# rel-cu.net
KiCad netlist of a schematic drawn in EAGLE
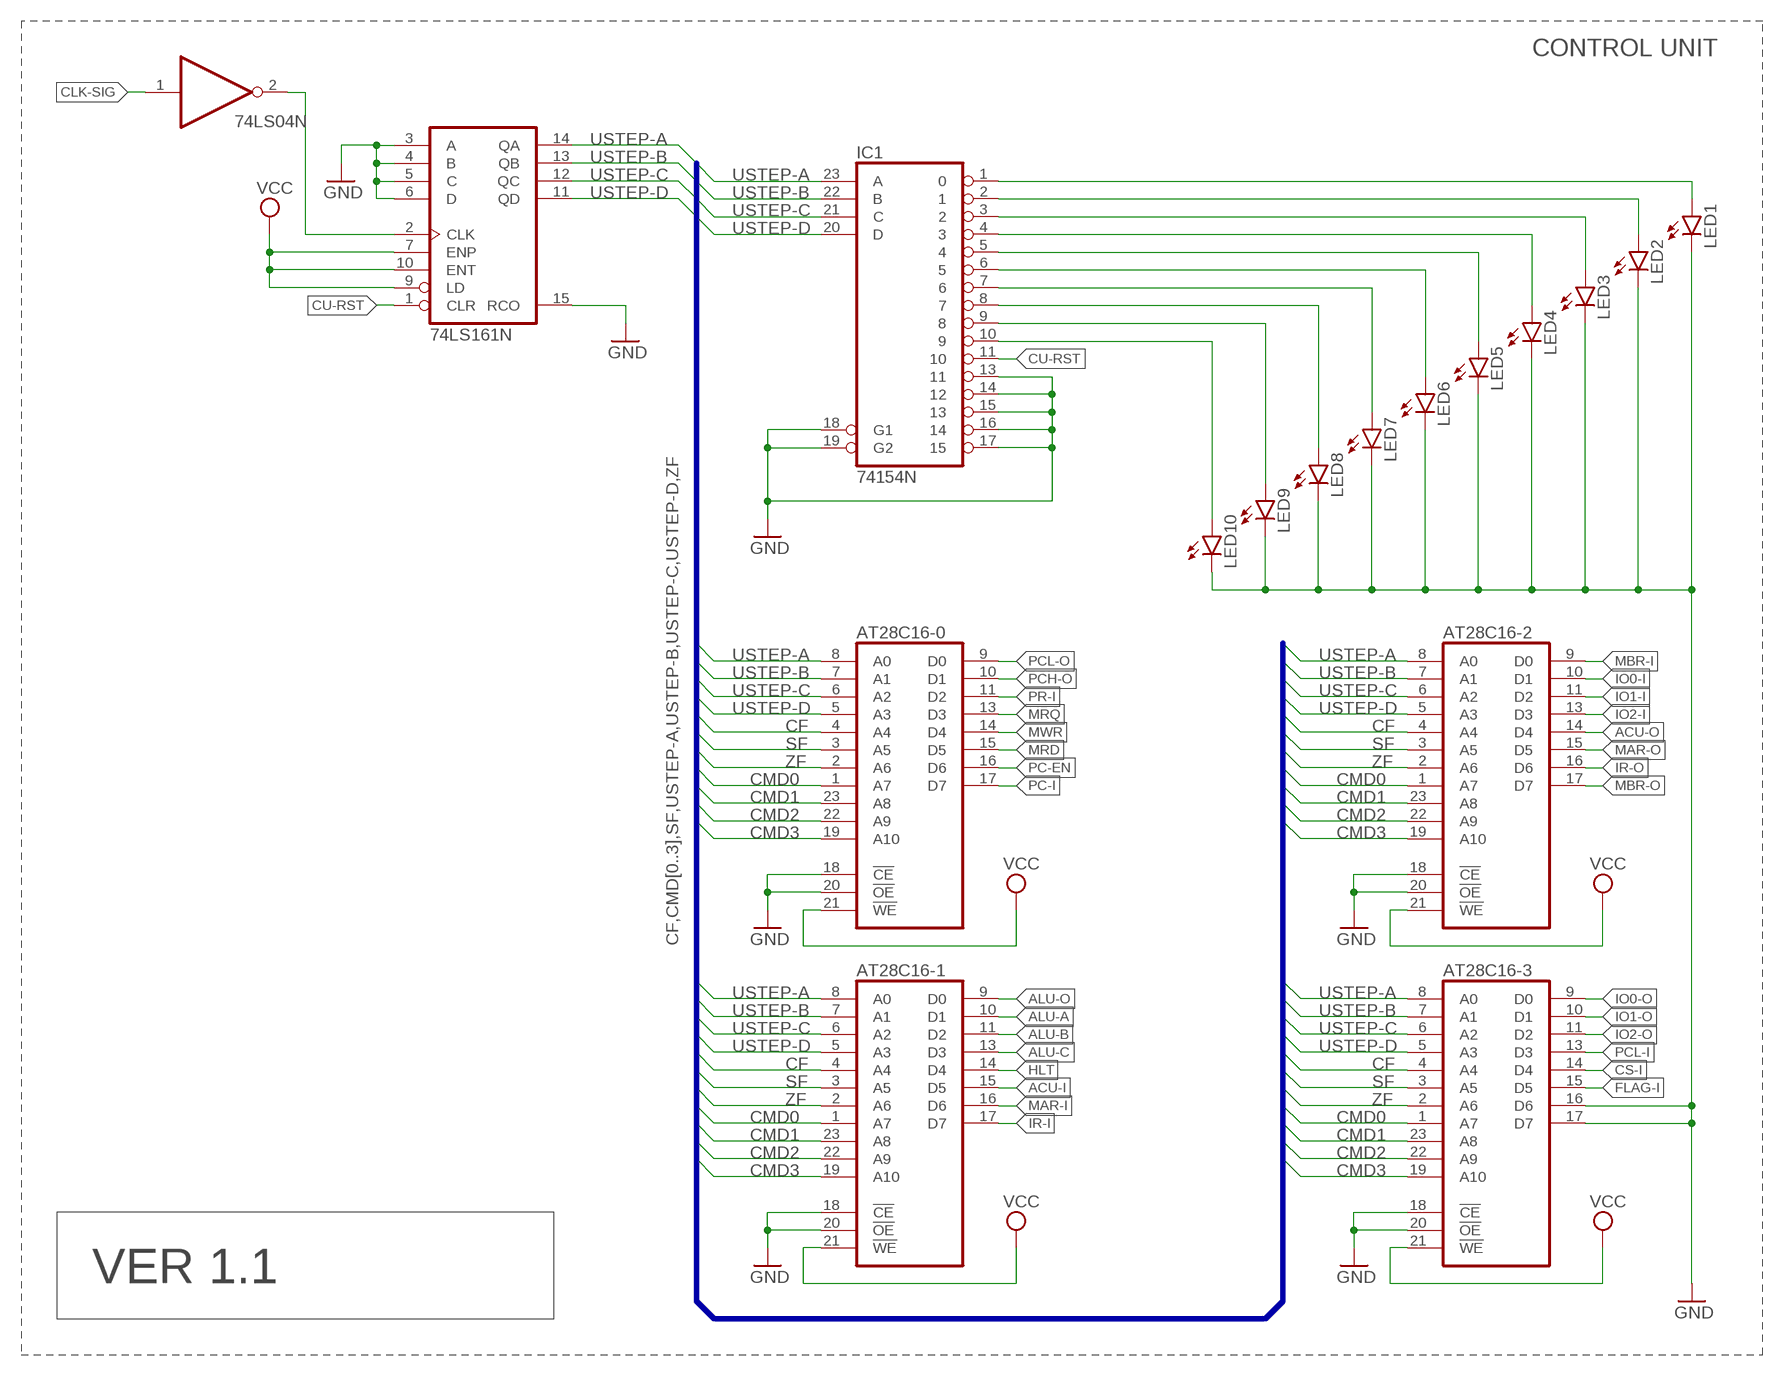
[diagram p0: schematic, sheet 1]

(export (version "E")
  (design (tool "Eeschema 10.0.6"))
  (components
    (comp (ref "74LS161N")
      (value "74160N")
      (footprint "eagle-import:DIL16")
      (libsource (lib "eagle-import") (part "74160N"))
    )
    (comp (ref "AT28C16-0")
      (value "2816")
      (footprint "eagle-import:DIL24")
      (libsource (lib "eagle-import") (part "2816"))
    )
    (comp (ref "AT28C16-1")
      (value "2816")
      (footprint "eagle-import:DIL24")
      (libsource (lib "eagle-import") (part "2816"))
    )
    (comp (ref "AT28C16-2")
      (value "2816")
      (footprint "eagle-import:DIL24")
      (libsource (lib "eagle-import") (part "2816"))
    )
    (comp (ref "AT28C16-3")
      (value "2816")
      (footprint "eagle-import:DIL24")
      (libsource (lib "eagle-import") (part "2816"))
    )
    (comp (ref "IC1")
      (value "74154N")
      (footprint "eagle-import:DIL24-6")
      (libsource (lib "eagle-import") (part "74154N"))
    )
    (comp (ref "IC2")
      (value "74LS04N")
      (footprint "eagle-import:DIL14")
      (libsource (lib "eagle-import") (part "7404NLS"))
    )
    (comp (ref "LED1")
      (value "LED5MM")
      (footprint "eagle-import:LED5MM")
      (libsource (lib "eagle-import") (part "LED5MM"))
    )
    (comp (ref "LED2")
      (value "LED5MM")
      (footprint "eagle-import:LED5MM")
      (libsource (lib "eagle-import") (part "LED5MM"))
    )
    (comp (ref "LED3")
      (value "LED5MM")
      (footprint "eagle-import:LED5MM")
      (libsource (lib "eagle-import") (part "LED5MM"))
    )
    (comp (ref "LED4")
      (value "LED5MM")
      (footprint "eagle-import:LED5MM")
      (libsource (lib "eagle-import") (part "LED5MM"))
    )
    (comp (ref "LED5")
      (value "LED5MM")
      (footprint "eagle-import:LED5MM")
      (libsource (lib "eagle-import") (part "LED5MM"))
    )
    (comp (ref "LED6")
      (value "LED5MM")
      (footprint "eagle-import:LED5MM")
      (libsource (lib "eagle-import") (part "LED5MM"))
    )
    (comp (ref "LED7")
      (value "LED5MM")
      (footprint "eagle-import:LED5MM")
      (libsource (lib "eagle-import") (part "LED5MM"))
    )
    (comp (ref "LED8")
      (value "LED5MM")
      (footprint "eagle-import:LED5MM")
      (libsource (lib "eagle-import") (part "LED5MM"))
    )
    (comp (ref "LED9")
      (value "LED5MM")
      (footprint "eagle-import:LED5MM")
      (libsource (lib "eagle-import") (part "LED5MM"))
    )
    (comp (ref "LED10")
      (value "LED5MM")
      (footprint "eagle-import:LED5MM")
      (libsource (lib "eagle-import") (part "LED5MM"))
    )
  )
  (nets
    (net (code "1") (name "/CF") (class "Default")
      (node (ref "AT28C16-0") (pin "4") (pinfunction "A4_4") (pintype "input"))
      (node (ref "AT28C16-1") (pin "4") (pinfunction "A4_4") (pintype "input"))
      (node (ref "AT28C16-2") (pin "4") (pinfunction "A4_4") (pintype "input"))
      (node (ref "AT28C16-3") (pin "4") (pinfunction "A4_4") (pintype "input"))
    )
    (net (code "2") (name "/CMD0") (class "Default")
      (node (ref "AT28C16-0") (pin "1") (pinfunction "A7_1") (pintype "input"))
      (node (ref "AT28C16-1") (pin "1") (pinfunction "A7_1") (pintype "input"))
      (node (ref "AT28C16-2") (pin "1") (pinfunction "A7_1") (pintype "input"))
      (node (ref "AT28C16-3") (pin "1") (pinfunction "A7_1") (pintype "input"))
    )
    (net (code "3") (name "/CMD1") (class "Default")
      (node (ref "AT28C16-0") (pin "23") (pinfunction "A8_23") (pintype "input"))
      (node (ref "AT28C16-1") (pin "23") (pinfunction "A8_23") (pintype "input"))
      (node (ref "AT28C16-2") (pin "23") (pinfunction "A8_23") (pintype "input"))
      (node (ref "AT28C16-3") (pin "23") (pinfunction "A8_23") (pintype "input"))
    )
    (net (code "4") (name "/CMD2") (class "Default")
      (node (ref "AT28C16-0") (pin "22") (pinfunction "A9_22") (pintype "input"))
      (node (ref "AT28C16-1") (pin "22") (pinfunction "A9_22") (pintype "input"))
      (node (ref "AT28C16-2") (pin "22") (pinfunction "A9_22") (pintype "input"))
      (node (ref "AT28C16-3") (pin "22") (pinfunction "A9_22") (pintype "input"))
    )
    (net (code "5") (name "/CMD3") (class "Default")
      (node (ref "AT28C16-0") (pin "19") (pinfunction "A10_19") (pintype "input"))
      (node (ref "AT28C16-1") (pin "19") (pinfunction "A10_19") (pintype "input"))
      (node (ref "AT28C16-2") (pin "19") (pinfunction "A10_19") (pintype "input"))
      (node (ref "AT28C16-3") (pin "19") (pinfunction "A10_19") (pintype "input"))
    )
    (net (code "6") (name "/SF") (class "Default")
      (node (ref "AT28C16-0") (pin "3") (pinfunction "A5_3") (pintype "input"))
      (node (ref "AT28C16-1") (pin "3") (pinfunction "A5_3") (pintype "input"))
      (node (ref "AT28C16-2") (pin "3") (pinfunction "A5_3") (pintype "input"))
      (node (ref "AT28C16-3") (pin "3") (pinfunction "A5_3") (pintype "input"))
    )
    (net (code "7") (name "/USTEP-A") (class "Default")
      (node (ref "74LS161N") (pin "14") (pinfunction "QA_14") (pintype "output"))
      (node (ref "AT28C16-0") (pin "8") (pinfunction "A0_8") (pintype "input"))
      (node (ref "AT28C16-1") (pin "8") (pinfunction "A0_8") (pintype "input"))
      (node (ref "AT28C16-2") (pin "8") (pinfunction "A0_8") (pintype "input"))
      (node (ref "AT28C16-3") (pin "8") (pinfunction "A0_8") (pintype "input"))
      (node (ref "IC1") (pin "23") (pinfunction "A_23") (pintype "input"))
    )
    (net (code "8") (name "/USTEP-B") (class "Default")
      (node (ref "74LS161N") (pin "13") (pinfunction "QB_13") (pintype "output"))
      (node (ref "AT28C16-0") (pin "7") (pinfunction "A1_7") (pintype "input"))
      (node (ref "AT28C16-1") (pin "7") (pinfunction "A1_7") (pintype "input"))
      (node (ref "AT28C16-2") (pin "7") (pinfunction "A1_7") (pintype "input"))
      (node (ref "AT28C16-3") (pin "7") (pinfunction "A1_7") (pintype "input"))
      (node (ref "IC1") (pin "22") (pinfunction "B_22") (pintype "input"))
    )
    (net (code "9") (name "/USTEP-C") (class "Default")
      (node (ref "74LS161N") (pin "12") (pinfunction "QC_12") (pintype "output"))
      (node (ref "AT28C16-0") (pin "6") (pinfunction "A2_6") (pintype "input"))
      (node (ref "AT28C16-1") (pin "6") (pinfunction "A2_6") (pintype "input"))
      (node (ref "AT28C16-2") (pin "6") (pinfunction "A2_6") (pintype "input"))
      (node (ref "AT28C16-3") (pin "6") (pinfunction "A2_6") (pintype "input"))
      (node (ref "IC1") (pin "21") (pinfunction "C_21") (pintype "input"))
    )
    (net (code "10") (name "/USTEP-D") (class "Default")
      (node (ref "74LS161N") (pin "11") (pinfunction "QD_11") (pintype "output"))
      (node (ref "AT28C16-0") (pin "5") (pinfunction "A3_5") (pintype "input"))
      (node (ref "AT28C16-1") (pin "5") (pinfunction "A3_5") (pintype "input"))
      (node (ref "AT28C16-2") (pin "5") (pinfunction "A3_5") (pintype "input"))
      (node (ref "AT28C16-3") (pin "5") (pinfunction "A3_5") (pintype "input"))
      (node (ref "IC1") (pin "20") (pinfunction "D_20") (pintype "input"))
    )
    (net (code "11") (name "/ZF") (class "Default")
      (node (ref "AT28C16-0") (pin "2") (pinfunction "A6_2") (pintype "input"))
      (node (ref "AT28C16-1") (pin "2") (pinfunction "A6_2") (pintype "input"))
      (node (ref "AT28C16-2") (pin "2") (pinfunction "A6_2") (pintype "input"))
      (node (ref "AT28C16-3") (pin "2") (pinfunction "A6_2") (pintype "input"))
    )
    (net (code "13") (name "ACU-I") (class "Default")
      (node (ref "AT28C16-1") (pin "15") (pinfunction "D5_15") (pintype "bidirectional"))
    )
    (net (code "14") (name "ACU-O") (class "Default")
      (node (ref "AT28C16-2") (pin "14") (pinfunction "D4_14") (pintype "bidirectional"))
    )
    (net (code "15") (name "ALU-A") (class "Default")
      (node (ref "AT28C16-1") (pin "10") (pinfunction "D1_10") (pintype "bidirectional"))
    )
    (net (code "16") (name "ALU-B") (class "Default")
      (node (ref "AT28C16-1") (pin "11") (pinfunction "D2_11") (pintype "bidirectional"))
    )
    (net (code "17") (name "ALU-C") (class "Default")
      (node (ref "AT28C16-1") (pin "13") (pinfunction "D3_13") (pintype "bidirectional"))
    )
    (net (code "18") (name "ALU-O") (class "Default")
      (node (ref "AT28C16-1") (pin "9") (pinfunction "D0_9") (pintype "bidirectional"))
    )
    (net (code "19") (name "CLK-SIG") (class "Default")
      (node (ref "74LS161N") (pin "2") (pinfunction "CLK_2") (pintype "input"))
      (node (ref "IC2") (pin "1") (pinfunction "I_1") (pintype "input"))
      (node (ref "IC2") (pin "2") (pinfunction "O_2") (pintype "output"))
    )
    (net (code "20") (name "CS-I") (class "Default")
      (node (ref "AT28C16-3") (pin "14") (pinfunction "D4_14") (pintype "bidirectional"))
    )
    (net (code "21") (name "CU-RST") (class "Default")
      (node (ref "74LS161N") (pin "1") (pinfunction "CLR_1") (pintype "input"))
      (node (ref "IC1") (pin "11") (pinfunction "10_11") (pintype "output"))
    )
    (net (code "22") (name "FLAG-I") (class "Default")
      (node (ref "AT28C16-3") (pin "15") (pinfunction "D5_15") (pintype "bidirectional"))
    )
    (net (code "23") (name "GND") (class "Default")
      (node (ref "74LS161N") (pin "15") (pinfunction "RCO_15") (pintype "output"))
      (node (ref "74LS161N") (pin "3") (pinfunction "A_3") (pintype "input"))
      (node (ref "74LS161N") (pin "4") (pinfunction "B_4") (pintype "input"))
      (node (ref "74LS161N") (pin "5") (pinfunction "C_5") (pintype "input"))
      (node (ref "74LS161N") (pin "6") (pinfunction "D_6") (pintype "input"))
      (node (ref "AT28C16-0") (pin "18") (pinfunction "~{CE}_18") (pintype "input"))
      (node (ref "AT28C16-0") (pin "20") (pinfunction "~{OE}_20") (pintype "input"))
      (node (ref "AT28C16-1") (pin "18") (pinfunction "~{CE}_18") (pintype "input"))
      (node (ref "AT28C16-1") (pin "20") (pinfunction "~{OE}_20") (pintype "input"))
      (node (ref "AT28C16-2") (pin "18") (pinfunction "~{CE}_18") (pintype "input"))
      (node (ref "AT28C16-2") (pin "20") (pinfunction "~{OE}_20") (pintype "input"))
      (node (ref "AT28C16-3") (pin "16") (pinfunction "D6_16") (pintype "bidirectional"))
      (node (ref "AT28C16-3") (pin "17") (pinfunction "D7_17") (pintype "bidirectional"))
      (node (ref "AT28C16-3") (pin "18") (pinfunction "~{CE}_18") (pintype "input"))
      (node (ref "AT28C16-3") (pin "20") (pinfunction "~{OE}_20") (pintype "input"))
      (node (ref "IC1") (pin "13") (pinfunction "11_13") (pintype "output"))
      (node (ref "IC1") (pin "14") (pinfunction "12_14") (pintype "output"))
      (node (ref "IC1") (pin "15") (pinfunction "13_15") (pintype "output"))
      (node (ref "IC1") (pin "16") (pinfunction "14_16") (pintype "output"))
      (node (ref "IC1") (pin "17") (pinfunction "15_17") (pintype "output"))
      (node (ref "IC1") (pin "18") (pinfunction "G1_18") (pintype "input"))
      (node (ref "IC1") (pin "19") (pinfunction "G2_19") (pintype "input"))
      (node (ref "LED1") (pin "K") (pinfunction "C_K") (pintype "passive"))
      (node (ref "LED10") (pin "K") (pinfunction "C_K") (pintype "passive"))
      (node (ref "LED2") (pin "K") (pinfunction "C_K") (pintype "passive"))
      (node (ref "LED3") (pin "K") (pinfunction "C_K") (pintype "passive"))
      (node (ref "LED4") (pin "K") (pinfunction "C_K") (pintype "passive"))
      (node (ref "LED5") (pin "K") (pinfunction "C_K") (pintype "passive"))
      (node (ref "LED6") (pin "K") (pinfunction "C_K") (pintype "passive"))
      (node (ref "LED7") (pin "K") (pinfunction "C_K") (pintype "passive"))
      (node (ref "LED8") (pin "K") (pinfunction "C_K") (pintype "passive"))
      (node (ref "LED9") (pin "K") (pinfunction "C_K") (pintype "passive"))
    )
    (net (code "24") (name "HLT") (class "Default")
      (node (ref "AT28C16-1") (pin "14") (pinfunction "D4_14") (pintype "bidirectional"))
    )
    (net (code "25") (name "IO0-I") (class "Default")
      (node (ref "AT28C16-2") (pin "10") (pinfunction "D1_10") (pintype "bidirectional"))
    )
    (net (code "26") (name "IO0-O") (class "Default")
      (node (ref "AT28C16-3") (pin "9") (pinfunction "D0_9") (pintype "bidirectional"))
    )
    (net (code "27") (name "IO1-I") (class "Default")
      (node (ref "AT28C16-2") (pin "11") (pinfunction "D2_11") (pintype "bidirectional"))
    )
    (net (code "28") (name "IO1-O") (class "Default")
      (node (ref "AT28C16-3") (pin "10") (pinfunction "D1_10") (pintype "bidirectional"))
    )
    (net (code "29") (name "IO2-I") (class "Default")
      (node (ref "AT28C16-2") (pin "13") (pinfunction "D3_13") (pintype "bidirectional"))
    )
    (net (code "30") (name "IO2-O") (class "Default")
      (node (ref "AT28C16-3") (pin "11") (pinfunction "D2_11") (pintype "bidirectional"))
    )
    (net (code "31") (name "IR-I") (class "Default")
      (node (ref "AT28C16-1") (pin "17") (pinfunction "D7_17") (pintype "bidirectional"))
    )
    (net (code "32") (name "IR-O") (class "Default")
      (node (ref "AT28C16-2") (pin "16") (pinfunction "D6_16") (pintype "bidirectional"))
    )
    (net (code "33") (name "MAR-I") (class "Default")
      (node (ref "AT28C16-1") (pin "16") (pinfunction "D6_16") (pintype "bidirectional"))
    )
    (net (code "34") (name "MAR-O") (class "Default")
      (node (ref "AT28C16-2") (pin "15") (pinfunction "D5_15") (pintype "bidirectional"))
    )
    (net (code "35") (name "MBR-I") (class "Default")
      (node (ref "AT28C16-2") (pin "9") (pinfunction "D0_9") (pintype "bidirectional"))
    )
    (net (code "36") (name "MBR-O") (class "Default")
      (node (ref "AT28C16-2") (pin "17") (pinfunction "D7_17") (pintype "bidirectional"))
    )
    (net (code "37") (name "MRD") (class "Default")
      (node (ref "AT28C16-0") (pin "15") (pinfunction "D5_15") (pintype "bidirectional"))
    )
    (net (code "38") (name "MRQ") (class "Default")
      (node (ref "AT28C16-0") (pin "13") (pinfunction "D3_13") (pintype "bidirectional"))
    )
    (net (code "39") (name "MWR") (class "Default")
      (node (ref "AT28C16-0") (pin "14") (pinfunction "D4_14") (pintype "bidirectional"))
    )
    (net (code "40") (name "Net-(IC1A-0)") (class "Default")
      (node (ref "IC1") (pin "1") (pinfunction "0_1") (pintype "output"))
      (node (ref "LED1") (pin "A") (pinfunction "A_A") (pintype "passive"))
    )
    (net (code "41") (name "Net-(IC1A-1)") (class "Default")
      (node (ref "IC1") (pin "2") (pinfunction "1_2") (pintype "output"))
      (node (ref "LED2") (pin "A") (pinfunction "A_A") (pintype "passive"))
    )
    (net (code "42") (name "Net-(IC1A-2)") (class "Default")
      (node (ref "IC1") (pin "3") (pinfunction "2_3") (pintype "output"))
      (node (ref "LED3") (pin "A") (pinfunction "A_A") (pintype "passive"))
    )
    (net (code "43") (name "Net-(IC1A-3)") (class "Default")
      (node (ref "IC1") (pin "4") (pinfunction "3_4") (pintype "output"))
      (node (ref "LED4") (pin "A") (pinfunction "A_A") (pintype "passive"))
    )
    (net (code "44") (name "Net-(IC1A-4)") (class "Default")
      (node (ref "IC1") (pin "5") (pinfunction "4_5") (pintype "output"))
      (node (ref "LED5") (pin "A") (pinfunction "A_A") (pintype "passive"))
    )
    (net (code "45") (name "Net-(IC1A-5)") (class "Default")
      (node (ref "IC1") (pin "6") (pinfunction "5_6") (pintype "output"))
      (node (ref "LED6") (pin "A") (pinfunction "A_A") (pintype "passive"))
    )
    (net (code "46") (name "Net-(IC1A-6)") (class "Default")
      (node (ref "IC1") (pin "7") (pinfunction "6_7") (pintype "output"))
      (node (ref "LED7") (pin "A") (pinfunction "A_A") (pintype "passive"))
    )
    (net (code "47") (name "Net-(IC1A-7)") (class "Default")
      (node (ref "IC1") (pin "8") (pinfunction "7_8") (pintype "output"))
      (node (ref "LED8") (pin "A") (pinfunction "A_A") (pintype "passive"))
    )
    (net (code "48") (name "Net-(IC1A-8)") (class "Default")
      (node (ref "IC1") (pin "9") (pinfunction "8_9") (pintype "output"))
      (node (ref "LED9") (pin "A") (pinfunction "A_A") (pintype "passive"))
    )
    (net (code "49") (name "Net-(IC1A-9)") (class "Default")
      (node (ref "IC1") (pin "10") (pinfunction "9_10") (pintype "output"))
      (node (ref "LED10") (pin "A") (pinfunction "A_A") (pintype "passive"))
    )
    (net (code "50") (name "PC-EN") (class "Default")
      (node (ref "AT28C16-0") (pin "16") (pinfunction "D6_16") (pintype "bidirectional"))
    )
    (net (code "51") (name "PC-I") (class "Default")
      (node (ref "AT28C16-0") (pin "17") (pinfunction "D7_17") (pintype "bidirectional"))
    )
    (net (code "52") (name "PCH-O") (class "Default")
      (node (ref "AT28C16-0") (pin "10") (pinfunction "D1_10") (pintype "bidirectional"))
    )
    (net (code "53") (name "PCL-I") (class "Default")
      (node (ref "AT28C16-3") (pin "13") (pinfunction "D3_13") (pintype "bidirectional"))
    )
    (net (code "54") (name "PCL-O") (class "Default")
      (node (ref "AT28C16-0") (pin "9") (pinfunction "D0_9") (pintype "bidirectional"))
    )
    (net (code "55") (name "PR-I") (class "Default")
      (node (ref "AT28C16-0") (pin "11") (pinfunction "D2_11") (pintype "bidirectional"))
    )
    (net (code "56") (name "VCC") (class "Default")
      (node (ref "74LS161N") (pin "10") (pinfunction "ENT_10") (pintype "input"))
      (node (ref "74LS161N") (pin "7") (pinfunction "ENP_7") (pintype "input"))
      (node (ref "74LS161N") (pin "9") (pinfunction "LD_9") (pintype "input"))
      (node (ref "AT28C16-0") (pin "21") (pinfunction "~{WE}_21") (pintype "input"))
      (node (ref "AT28C16-1") (pin "21") (pinfunction "~{WE}_21") (pintype "input"))
      (node (ref "AT28C16-2") (pin "21") (pinfunction "~{WE}_21") (pintype "input"))
      (node (ref "AT28C16-3") (pin "21") (pinfunction "~{WE}_21") (pintype "input"))
    )
  )
)
